# 5_-Motor_Driver_Schematic.net
KiCad netlist of a schematic drawn in Altium Designer
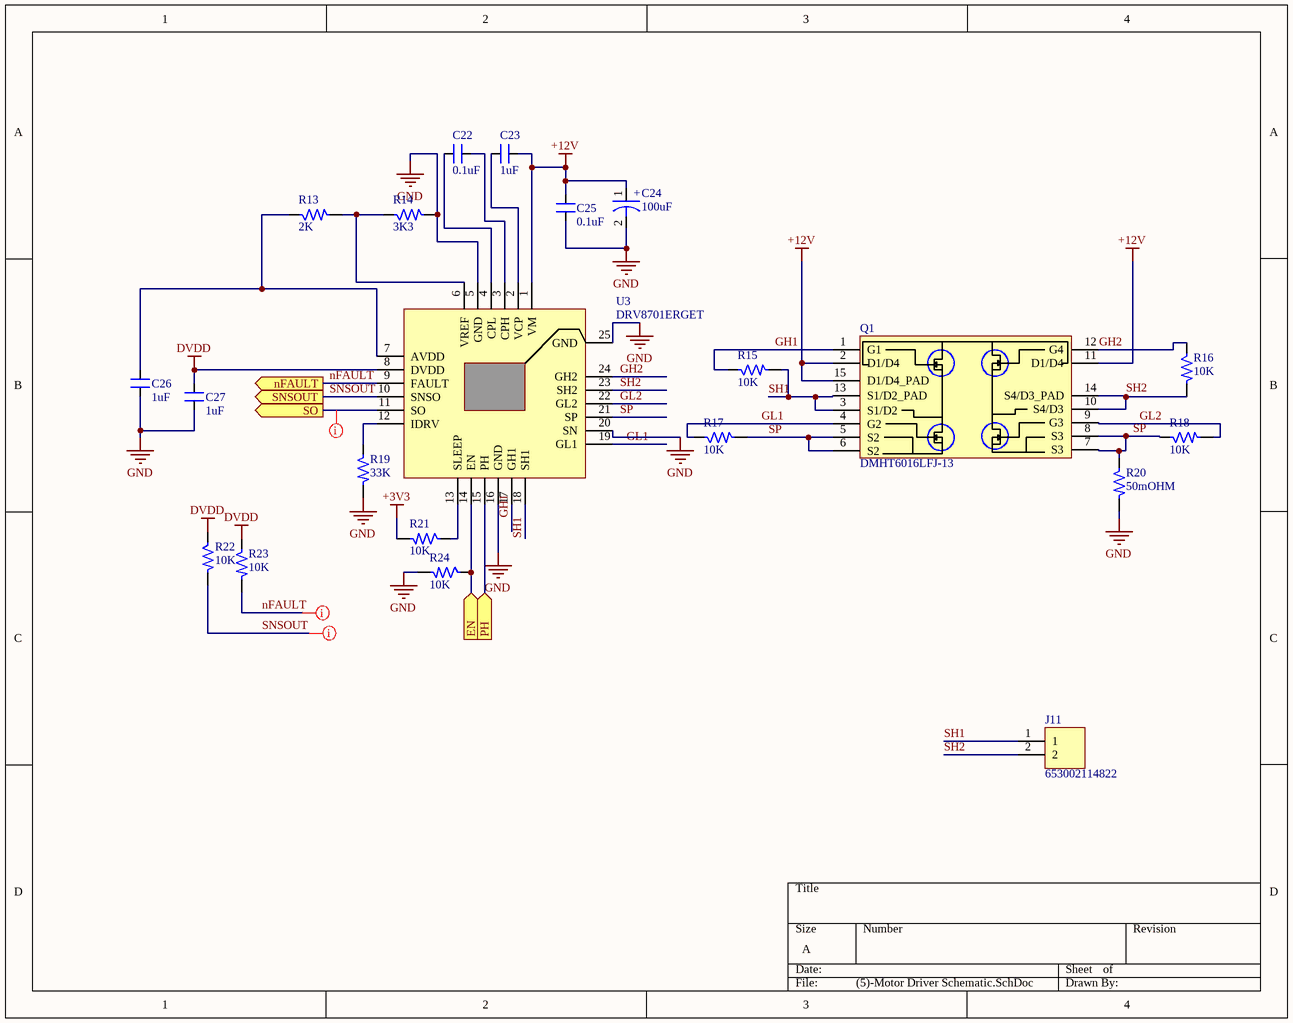
[diagram p0: (5)-Motor Driver Schematic.SchDoc]

(export (version "E")
  (design (tool "Eeschema 10.0.6"))
  (components
    (comp (ref "C22")
      (value "0.1uF")
      (footprint "CAP_0805")
      (description "0.1µF ±10% 50V Ceramic Capacitor X7R 0805 (2012 Metric)")
      (fields
        (field (name "MANUFACTURER") "Samsung")
        (field (name "MANUFACTURER PART NUMBER") "CL21B104KBCNNNC")
      )
      (libsource (lib "ESTEEMPCBLIB") (part "CAP_0.1uF-50V-10%-0805"))
    )
    (comp (ref "C23")
      (value "1uF")
      (footprint "CAP_0805")
      (description "1µF ±5% 50V Ceramic Capacitor X7R 0805 (2012 Metric)")
      (fields
        (field (name "MANUFACTURER") "Samsung")
        (field (name "MANUFACTURER PART NUMBER") "CC0805JKX7R9BB105")
      )
      (libsource (lib "ESTEEMPCBLIB") (part "CAP_1uF-50V-5%-0805"))
    )
    (comp (ref "C24")
      (value "100uF")
      (footprint "ACAP_P236_D305_H303_RAD")
      (description "100µF 25V Aluminum Electrolytic Capacitors Radial, Can - SMD 1000 Hrs @ 105°C")
      (fields
        (field (name "MANUFACTURER") "Nichicon")
        (field (name "MANUFACTURER PART NUMBER") "UWT1E101MCL1GS")
      )
      (libsource (lib "ESTEEMPCBLIB") (part "CAP-P_100uF-25V-20%-RAD"))
    )
    (comp (ref "C25")
      (value "0.1uF")
      (footprint "CAP_0805")
      (description "0.1µF ±10% 50V Ceramic Capacitor X7R 0805 (2012 Metric)")
      (fields
        (field (name "MANUFACTURER") "Samsung")
        (field (name "MANUFACTURER PART NUMBER") "CL21B104KBCNNNC")
      )
      (libsource (lib "ESTEEMPCBLIB") (part "CAP_0.1uF-50V-10%-0805"))
    )
    (comp (ref "C26")
      (value "1uF")
      (footprint "CAP_0805")
      (description "1µF ±5% 50V Ceramic Capacitor X7R 0805 (2012 Metric)")
      (fields
        (field (name "MANUFACTURER") "Samsung")
        (field (name "MANUFACTURER PART NUMBER") "CC0805JKX7R9BB105")
      )
      (libsource (lib "ESTEEMPCBLIB") (part "CAP_1uF-50V-5%-0805"))
    )
    (comp (ref "C27")
      (value "1uF")
      (footprint "CAP_0805")
      (description "1µF ±5% 50V Ceramic Capacitor X7R 0805 (2012 Metric)")
      (fields
        (field (name "MANUFACTURER") "Samsung")
        (field (name "MANUFACTURER PART NUMBER") "CC0805JKX7R9BB105")
      )
      (libsource (lib "ESTEEMPCBLIB") (part "CAP_1uF-50V-5%-0805"))
    )
    (comp (ref "J11")
      (value "653002114822")
      (footprint "CON2_50_653002114822_TH_ST")
      (description "2 Pins, 1 Row 1.25mm Pitch, Straight Connector, male")
      (fields (field (name "MANUFACTURER") "JST") (field (name "MATING PART NUMBER") "653002113322"))
      (libsource (lib "ESTEEMPCBLIB") (part "CON-PLG_2X1-50-ST-TH"))
    )
    (comp (ref "Q1")
      (value "DMHT6016LFJ-13")
      (footprint "DFN5045-12_33_212_27X15_SMD_1")
      (description "Mosfet Array 4 N-Channel 14.8A (Ta) Surface Mount V-DFN5045-12")
      (fields (field (name "MANUFACTURER") "ON Semiconductor"))
      (libsource (lib "ESTEEMPCBLIB") (part "MOSFET-N_60V-14.8A-V-DFN5045-12"))
    )
    (comp (ref "R13")
      (value "2K")
      (footprint "RES_0603")
      (fields
        (field (name "MANUFACTURER") "Stackpole Electronics")
        (field (name "MANUFACTURER PART NUMBER") "RNCP0603FTD2K00")
      )
      (libsource (lib "ESTEEMPCBLIB") (part "RES_2K-0.125W-1%-0603"))
    )
    (comp (ref "R14")
      (value "3K3")
      (footprint "RES_0603")
      (description "3.3 kOhms ±1% 0.1W, 1/10W Chip Resistor 0603 (1608 Metric) Automotive AEC-Q200 Thick Film")
      (fields (field (name "MANUFACTURER") "Wilson") (field (name "MANUFACTURER PART NUMBER") "WR06X3301FTL"))
      (libsource (lib "ESTEEMPCBLIB") (part "RES_3.3K-0.1W-1%-0603"))
    )
    (comp (ref "R15")
      (value "10K")
      (footprint "RES_0603")
      (description "10 kOhms ±1% 0.1W, 1/10W Chip Resistor 0603 (1608 Metric) Automotive AEC-Q200 Thick Film")
      (fields (field (name "MANUFACTURER") "Walsin") (field (name "MANUFACTURER PART NUMBER") "WR06X1002FTL"))
      (libsource (lib "ESTEEMPCBLIB") (part "RES_10K-0.1W-1%-0603"))
    )
    (comp (ref "R16")
      (value "10K")
      (footprint "RES_0603")
      (description "10 kOhms ±1% 0.1W, 1/10W Chip Resistor 0603 (1608 Metric) Automotive AEC-Q200 Thick Film")
      (fields (field (name "MANUFACTURER") "Walsin") (field (name "MANUFACTURER PART NUMBER") "WR06X1002FTL"))
      (libsource (lib "ESTEEMPCBLIB") (part "RES_10K-0.1W-1%-0603"))
    )
    (comp (ref "R17")
      (value "10K")
      (footprint "RES_0603")
      (description "10 kOhms ±1% 0.1W, 1/10W Chip Resistor 0603 (1608 Metric) Automotive AEC-Q200 Thick Film")
      (fields (field (name "MANUFACTURER") "Walsin") (field (name "MANUFACTURER PART NUMBER") "WR06X1002FTL"))
      (libsource (lib "ESTEEMPCBLIB") (part "RES_10K-0.1W-1%-0603"))
    )
    (comp (ref "R18")
      (value "10K")
      (footprint "RES_0603")
      (description "10 kOhms ±1% 0.1W, 1/10W Chip Resistor 0603 (1608 Metric) Automotive AEC-Q200 Thick Film")
      (fields (field (name "MANUFACTURER") "Walsin") (field (name "MANUFACTURER PART NUMBER") "WR06X1002FTL"))
      (libsource (lib "ESTEEMPCBLIB") (part "RES_10K-0.1W-1%-0603"))
    )
    (comp (ref "R19")
      (value "33K")
      (footprint "RES_0805")
      (fields
        (field (name "MANUFACTURER") "Vishay BCcomponents")
        (field (name "MANUFACTURER PART NUMBER") "CRG0805F33K")
      )
      (libsource (lib "ESTEEMPCBLIB") (part "RES_33K-0.125W-1%-0805"))
    )
    (comp (ref "R20")
      (value "50mOHM")
      (footprint "RES_2512")
      (fields
        (field (name "MANUFACTURER") "Yageo")
        (field (name "MANUFACTURER PART NUMBER") "PA2512FKF7W0R05E")
      )
      (libsource (lib "ESTEEMPCBLIB") (part "RES_50mOhm-2W-1%-2512"))
    )
    (comp (ref "R21")
      (value "10K")
      (footprint "RES_0603")
      (description "10 kOhms ±1% 0.1W, 1/10W Chip Resistor 0603 (1608 Metric) Automotive AEC-Q200 Thick Film")
      (fields (field (name "MANUFACTURER") "Walsin") (field (name "MANUFACTURER PART NUMBER") "WR06X1002FTL"))
      (libsource (lib "ESTEEMPCBLIB") (part "RES_10K-0.1W-1%-0603"))
    )
    (comp (ref "R22")
      (value "10K")
      (footprint "RES_0603")
      (description "10 kOhms ±1% 0.1W, 1/10W Chip Resistor 0603 (1608 Metric) Automotive AEC-Q200 Thick Film")
      (fields (field (name "MANUFACTURER") "Walsin") (field (name "MANUFACTURER PART NUMBER") "WR06X1002FTL"))
      (libsource (lib "ESTEEMPCBLIB") (part "RES_10K-0.1W-1%-0603"))
    )
    (comp (ref "R23")
      (value "10K")
      (footprint "RES_0603")
      (description "10 kOhms ±1% 0.1W, 1/10W Chip Resistor 0603 (1608 Metric) Automotive AEC-Q200 Thick Film")
      (fields (field (name "MANUFACTURER") "Walsin") (field (name "MANUFACTURER PART NUMBER") "WR06X1002FTL"))
      (libsource (lib "ESTEEMPCBLIB") (part "RES_10K-0.1W-1%-0603"))
    )
    (comp (ref "R24")
      (value "10K")
      (footprint "RES_0603")
      (description "10 kOhms ±1% 0.1W, 1/10W Chip Resistor 0603 (1608 Metric) Automotive AEC-Q200 Thick Film")
      (fields (field (name "MANUFACTURER") "Walsin") (field (name "MANUFACTURER PART NUMBER") "WR06X1002FTL"))
      (libsource (lib "ESTEEMPCBLIB") (part "RES_10K-0.1W-1%-0603"))
    )
    (comp (ref "U3")
      (value "DRV8701ERGET")
      (footprint "VFQFN24_19.6_196_12X32_SMD_1")
      (description "Motor Driver Power MOSFET Parallel 24-VQFN (4x4)")
      (fields (field (name "MANUFACTURER") "Texas Instruments"))
      (libsource (lib "ESTEEMPCBLIB") (part "IC_DRV8701ERGET"))
    )
  )
  (nets
    (net (code "1") (name "+3V3") (class "Default")
      (node (ref "R21") (pin "2") (pinfunction "2_2") (pintype "passive"))
    )
    (net (code "2") (name "+12V") (class "Default")
      (node (ref "C23") (pin "2") (pinfunction "2_2") (pintype "passive"))
      (node (ref "C24") (pin "1") (pinfunction "1_1") (pintype "passive"))
      (node (ref "C25") (pin "1") (pinfunction "1_1") (pintype "passive"))
      (node (ref "Q1") (pin "11") (pinfunction "D1/D4_11") (pintype "passive"))
      (node (ref "Q1") (pin "15") (pinfunction "D1/D4_PAD_15") (pintype "passive"))
      (node (ref "Q1") (pin "2") (pinfunction "D1/D4_2") (pintype "passive"))
      (node (ref "U3") (pin "1") (pinfunction "VM_1") (pintype "passive"))
    )
    (net (code "3") (name "/EN") (class "Default")
      (node (ref "R24") (pin "1") (pinfunction "1_1") (pintype "passive"))
      (node (ref "U3") (pin "14") (pinfunction "EN_14") (pintype "passive"))
    )
    (net (code "4") (name "/GH1") (class "Default")
      (node (ref "Q1") (pin "1") (pinfunction "G1_1") (pintype "passive"))
      (node (ref "R15") (pin "1") (pinfunction "1_1") (pintype "passive"))
      (node (ref "U3") (pin "17") (pinfunction "GH1_17") (pintype "passive"))
    )
    (net (code "5") (name "/GH2") (class "Default")
      (node (ref "Q1") (pin "12") (pinfunction "G4_12") (pintype "passive"))
      (node (ref "R16") (pin "1") (pinfunction "1_1") (pintype "passive"))
      (node (ref "U3") (pin "24") (pinfunction "GH2_24") (pintype "passive"))
    )
    (net (code "6") (name "/GL1") (class "Default")
      (node (ref "Q1") (pin "4") (pinfunction "G2_4") (pintype "passive"))
      (node (ref "R17") (pin "1") (pinfunction "1_1") (pintype "passive"))
      (node (ref "U3") (pin "19") (pinfunction "GL1_19") (pintype "passive"))
    )
    (net (code "7") (name "/GL2") (class "Default")
      (node (ref "Q1") (pin "9") (pinfunction "G3_9") (pintype "passive"))
      (node (ref "R18") (pin "2") (pinfunction "2_2") (pintype "passive"))
      (node (ref "U3") (pin "22") (pinfunction "GL2_22") (pintype "passive"))
    )
    (net (code "8") (name "/PH") (class "Default")
      (node (ref "U3") (pin "15") (pinfunction "PH_15") (pintype "passive"))
    )
    (net (code "9") (name "/SH1") (class "Default")
      (node (ref "J11") (pin "1") (pinfunction "1_1") (pintype "passive"))
      (node (ref "Q1") (pin "13") (pinfunction "S1/D2_PAD_13") (pintype "passive"))
      (node (ref "Q1") (pin "3") (pinfunction "S1/D2_3") (pintype "passive"))
      (node (ref "R15") (pin "2") (pinfunction "2_2") (pintype "passive"))
      (node (ref "U3") (pin "18") (pinfunction "SH1_18") (pintype "passive"))
    )
    (net (code "10") (name "/SH2") (class "Default")
      (node (ref "J11") (pin "2") (pinfunction "2_2") (pintype "passive"))
      (node (ref "Q1") (pin "10") (pinfunction "S4/D3_10") (pintype "passive"))
      (node (ref "Q1") (pin "14") (pinfunction "S4/D3_PAD_14") (pintype "passive"))
      (node (ref "R16") (pin "2") (pinfunction "2_2") (pintype "passive"))
      (node (ref "U3") (pin "23") (pinfunction "SH2_23") (pintype "passive"))
    )
    (net (code "11") (name "/SNSOUT") (class "Default")
      (node (ref "R22") (pin "2") (pinfunction "2_2") (pintype "passive"))
      (node (ref "U3") (pin "10") (pinfunction "SNSO_10") (pintype "passive"))
    )
    (net (code "12") (name "/SO") (class "Default")
      (node (ref "U3") (pin "11") (pinfunction "SO_11") (pintype "passive"))
    )
    (net (code "13") (name "/SP") (class "Default")
      (node (ref "Q1") (pin "5") (pinfunction "S2_5") (pintype "passive"))
      (node (ref "Q1") (pin "6") (pinfunction "S2_6") (pintype "passive"))
      (node (ref "Q1") (pin "7") (pinfunction "S3_7") (pintype "passive"))
      (node (ref "Q1") (pin "8") (pinfunction "S3_8") (pintype "passive"))
      (node (ref "R17") (pin "2") (pinfunction "2_2") (pintype "passive"))
      (node (ref "R18") (pin "1") (pinfunction "1_1") (pintype "passive"))
      (node (ref "R20") (pin "1") (pinfunction "1_1") (pintype "passive"))
      (node (ref "U3") (pin "21") (pinfunction "SP_21") (pintype "passive"))
    )
    (net (code "14") (name "/nFAULT") (class "Default")
      (node (ref "R23") (pin "2") (pinfunction "2_2") (pintype "passive"))
      (node (ref "U3") (pin "9") (pinfunction "FAULT_9") (pintype "passive"))
    )
    (net (code "15") (name "DVDD") (class "Default")
      (node (ref "C27") (pin "1") (pinfunction "1_1") (pintype "passive"))
      (node (ref "R22") (pin "1") (pinfunction "1_1") (pintype "passive"))
      (node (ref "R23") (pin "1") (pinfunction "1_1") (pintype "passive"))
      (node (ref "U3") (pin "8") (pinfunction "DVDD_8") (pintype "passive"))
    )
    (net (code "16") (name "GND") (class "Default")
      (node (ref "C24") (pin "2") (pinfunction "2_2") (pintype "passive"))
      (node (ref "C25") (pin "2") (pinfunction "2_2") (pintype "passive"))
      (node (ref "C26") (pin "2") (pinfunction "2_2") (pintype "passive"))
      (node (ref "C27") (pin "2") (pinfunction "2_2") (pintype "passive"))
      (node (ref "R14") (pin "2") (pinfunction "2_2") (pintype "passive"))
      (node (ref "R19") (pin "2") (pinfunction "2_2") (pintype "passive"))
      (node (ref "R20") (pin "2") (pinfunction "2_2") (pintype "passive"))
      (node (ref "R24") (pin "2") (pinfunction "2_2") (pintype "passive"))
      (node (ref "U3") (pin "16") (pinfunction "GND_16") (pintype "passive"))
      (node (ref "U3") (pin "20") (pinfunction "SN_20") (pintype "passive"))
      (node (ref "U3") (pin "25") (pinfunction "GND_25") (pintype "passive"))
      (node (ref "U3") (pin "5") (pinfunction "GND_5") (pintype "passive"))
    )
    (net (code "17") (name "Net-(U3-AVDD)") (class "Default")
      (node (ref "C26") (pin "1") (pinfunction "1_1") (pintype "passive"))
      (node (ref "R13") (pin "1") (pinfunction "1_1") (pintype "passive"))
      (node (ref "U3") (pin "7") (pinfunction "AVDD_7") (pintype "passive"))
    )
    (net (code "18") (name "Net-(U3-CPH)") (class "Default")
      (node (ref "C22") (pin "1") (pinfunction "1_1") (pintype "passive"))
      (node (ref "U3") (pin "3") (pinfunction "CPH_3") (pintype "passive"))
    )
    (net (code "19") (name "Net-(U3-CPL)") (class "Default")
      (node (ref "C22") (pin "2") (pinfunction "2_2") (pintype "passive"))
      (node (ref "U3") (pin "4") (pinfunction "CPL_4") (pintype "passive"))
    )
    (net (code "20") (name "Net-(U3-IDRV)") (class "Default")
      (node (ref "R19") (pin "1") (pinfunction "1_1") (pintype "passive"))
      (node (ref "U3") (pin "12") (pinfunction "IDRV_12") (pintype "passive"))
    )
    (net (code "21") (name "Net-(U3-SLEEP)") (class "Default")
      (node (ref "R21") (pin "1") (pinfunction "1_1") (pintype "passive"))
      (node (ref "U3") (pin "13") (pinfunction "SLEEP_13") (pintype "passive"))
    )
    (net (code "22") (name "Net-(U3-VCP)") (class "Default")
      (node (ref "C23") (pin "1") (pinfunction "1_1") (pintype "passive"))
      (node (ref "U3") (pin "2") (pinfunction "VCP_2") (pintype "passive"))
    )
    (net (code "23") (name "Net-(U3-VREF)") (class "Default")
      (node (ref "R13") (pin "2") (pinfunction "2_2") (pintype "passive"))
      (node (ref "R14") (pin "1") (pinfunction "1_1") (pintype "passive"))
      (node (ref "U3") (pin "6") (pinfunction "VREF_6") (pintype "passive"))
    )
  )
)
